# leds.net
KiCad netlist of a schematic drawn in Altium Designer
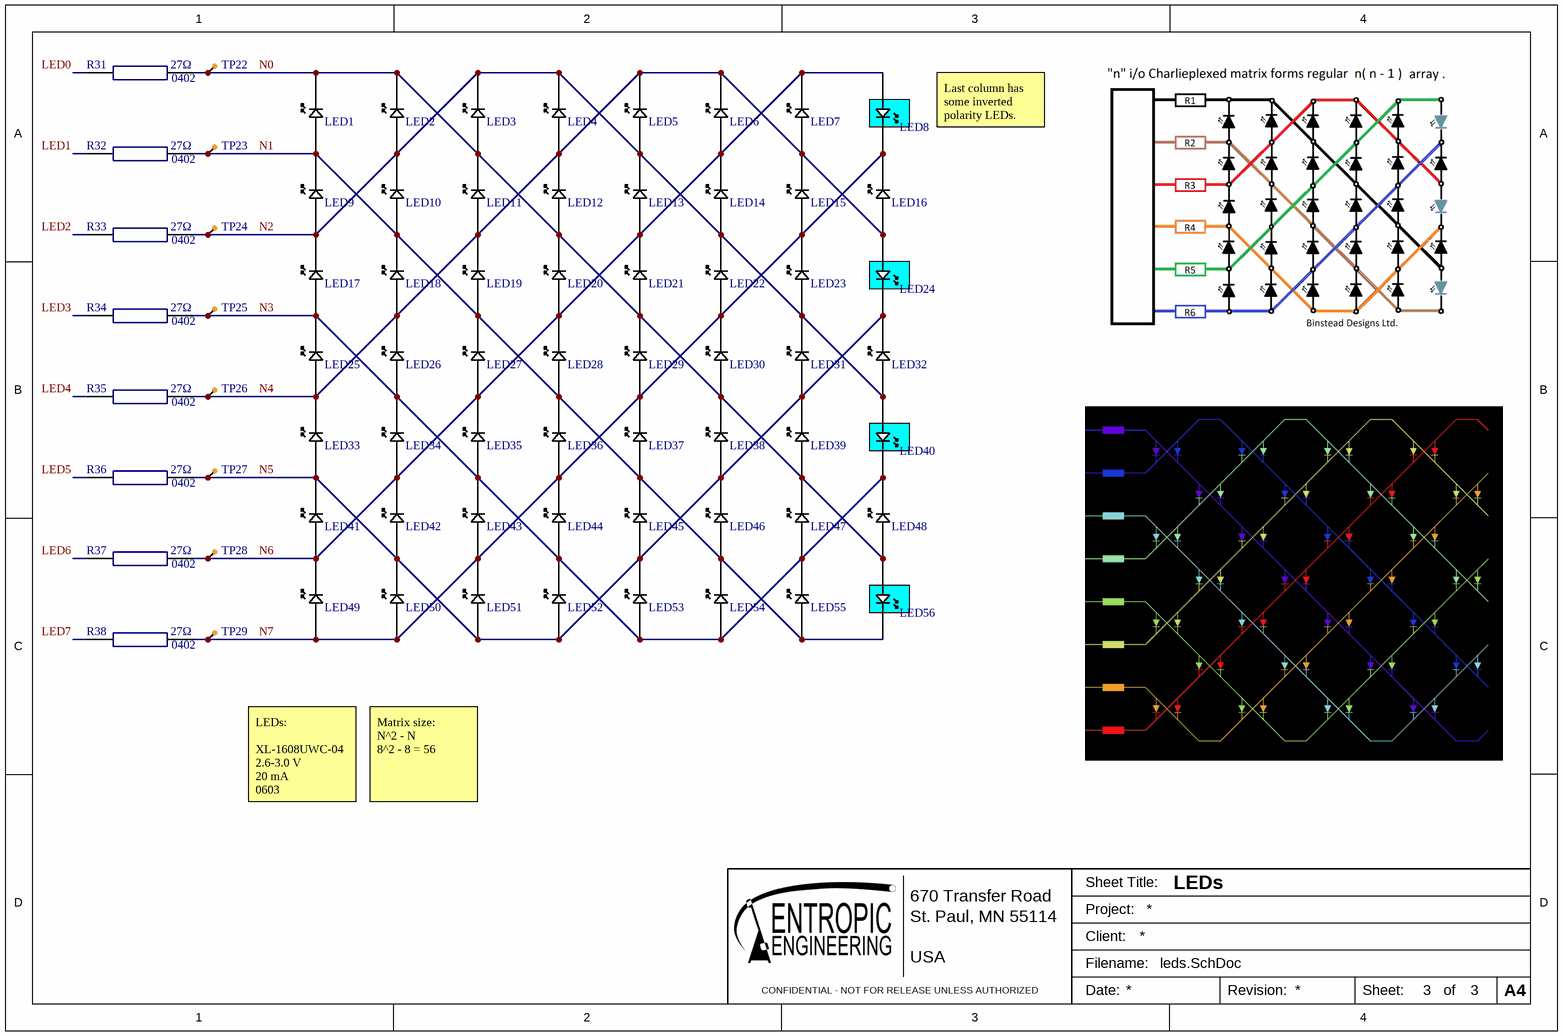
[diagram p0: leds.SchDoc]

(export (version "E")
  (design (tool "Eeschema 10.0.6"))
  (components
    (comp (ref "LED1")
      (value "XL-1608UWC-04")
      (footprint "0603_LED")
      (description "White LED, 0603")
      (fields (field (name "MANUFACTURER") "XINGLIGHT"))
      (libsource (lib "lamp_controller") (part "XL-1608UWC-04"))
    )
    (comp (ref "LED2")
      (value "XL-1608UWC-04")
      (footprint "0603_LED")
      (description "White LED, 0603")
      (fields (field (name "MANUFACTURER") "XINGLIGHT"))
      (libsource (lib "lamp_controller") (part "XL-1608UWC-04"))
    )
    (comp (ref "LED3")
      (value "XL-1608UWC-04")
      (footprint "0603_LED")
      (description "White LED, 0603")
      (fields (field (name "MANUFACTURER") "XINGLIGHT"))
      (libsource (lib "lamp_controller") (part "XL-1608UWC-04"))
    )
    (comp (ref "LED4")
      (value "XL-1608UWC-04")
      (footprint "0603_LED")
      (description "White LED, 0603")
      (fields (field (name "MANUFACTURER") "XINGLIGHT"))
      (libsource (lib "lamp_controller") (part "XL-1608UWC-04"))
    )
    (comp (ref "LED5")
      (value "XL-1608UWC-04")
      (footprint "0603_LED")
      (description "White LED, 0603")
      (fields (field (name "MANUFACTURER") "XINGLIGHT"))
      (libsource (lib "lamp_controller") (part "XL-1608UWC-04"))
    )
    (comp (ref "LED6")
      (value "XL-1608UWC-04")
      (footprint "0603_LED")
      (description "White LED, 0603")
      (fields (field (name "MANUFACTURER") "XINGLIGHT"))
      (libsource (lib "lamp_controller") (part "XL-1608UWC-04"))
    )
    (comp (ref "LED7")
      (value "XL-1608UWC-04")
      (footprint "0603_LED")
      (description "White LED, 0603")
      (fields (field (name "MANUFACTURER") "XINGLIGHT"))
      (libsource (lib "lamp_controller") (part "XL-1608UWC-04"))
    )
    (comp (ref "LED8")
      (value "XL-1608UWC-04")
      (footprint "0603_LED")
      (description "White LED, 0603")
      (fields (field (name "MANUFACTURER") "XINGLIGHT"))
      (libsource (lib "lamp_controller") (part "XL-1608UWC-04"))
    )
    (comp (ref "LED9")
      (value "XL-1608UWC-04")
      (footprint "0603_LED")
      (description "White LED, 0603")
      (fields (field (name "MANUFACTURER") "XINGLIGHT"))
      (libsource (lib "lamp_controller") (part "XL-1608UWC-04"))
    )
    (comp (ref "LED10")
      (value "XL-1608UWC-04")
      (footprint "0603_LED")
      (description "White LED, 0603")
      (fields (field (name "MANUFACTURER") "XINGLIGHT"))
      (libsource (lib "lamp_controller") (part "XL-1608UWC-04"))
    )
    (comp (ref "LED11")
      (value "XL-1608UWC-04")
      (footprint "0603_LED")
      (description "White LED, 0603")
      (fields (field (name "MANUFACTURER") "XINGLIGHT"))
      (libsource (lib "lamp_controller") (part "XL-1608UWC-04"))
    )
    (comp (ref "LED12")
      (value "XL-1608UWC-04")
      (footprint "0603_LED")
      (description "White LED, 0603")
      (fields (field (name "MANUFACTURER") "XINGLIGHT"))
      (libsource (lib "lamp_controller") (part "XL-1608UWC-04"))
    )
    (comp (ref "LED13")
      (value "XL-1608UWC-04")
      (footprint "0603_LED")
      (description "White LED, 0603")
      (fields (field (name "MANUFACTURER") "XINGLIGHT"))
      (libsource (lib "lamp_controller") (part "XL-1608UWC-04"))
    )
    (comp (ref "LED14")
      (value "XL-1608UWC-04")
      (footprint "0603_LED")
      (description "White LED, 0603")
      (fields (field (name "MANUFACTURER") "XINGLIGHT"))
      (libsource (lib "lamp_controller") (part "XL-1608UWC-04"))
    )
    (comp (ref "LED15")
      (value "XL-1608UWC-04")
      (footprint "0603_LED")
      (description "White LED, 0603")
      (fields (field (name "MANUFACTURER") "XINGLIGHT"))
      (libsource (lib "lamp_controller") (part "XL-1608UWC-04"))
    )
    (comp (ref "LED16")
      (value "XL-1608UWC-04")
      (footprint "0603_LED")
      (description "White LED, 0603")
      (fields (field (name "MANUFACTURER") "XINGLIGHT"))
      (libsource (lib "lamp_controller") (part "XL-1608UWC-04"))
    )
    (comp (ref "LED17")
      (value "XL-1608UWC-04")
      (footprint "0603_LED")
      (description "White LED, 0603")
      (fields (field (name "MANUFACTURER") "XINGLIGHT"))
      (libsource (lib "lamp_controller") (part "XL-1608UWC-04"))
    )
    (comp (ref "LED18")
      (value "XL-1608UWC-04")
      (footprint "0603_LED")
      (description "White LED, 0603")
      (fields (field (name "MANUFACTURER") "XINGLIGHT"))
      (libsource (lib "lamp_controller") (part "XL-1608UWC-04"))
    )
    (comp (ref "LED19")
      (value "XL-1608UWC-04")
      (footprint "0603_LED")
      (description "White LED, 0603")
      (fields (field (name "MANUFACTURER") "XINGLIGHT"))
      (libsource (lib "lamp_controller") (part "XL-1608UWC-04"))
    )
    (comp (ref "LED20")
      (value "XL-1608UWC-04")
      (footprint "0603_LED")
      (description "White LED, 0603")
      (fields (field (name "MANUFACTURER") "XINGLIGHT"))
      (libsource (lib "lamp_controller") (part "XL-1608UWC-04"))
    )
    (comp (ref "LED21")
      (value "XL-1608UWC-04")
      (footprint "0603_LED")
      (description "White LED, 0603")
      (fields (field (name "MANUFACTURER") "XINGLIGHT"))
      (libsource (lib "lamp_controller") (part "XL-1608UWC-04"))
    )
    (comp (ref "LED22")
      (value "XL-1608UWC-04")
      (footprint "0603_LED")
      (description "White LED, 0603")
      (fields (field (name "MANUFACTURER") "XINGLIGHT"))
      (libsource (lib "lamp_controller") (part "XL-1608UWC-04"))
    )
    (comp (ref "LED23")
      (value "XL-1608UWC-04")
      (footprint "0603_LED")
      (description "White LED, 0603")
      (fields (field (name "MANUFACTURER") "XINGLIGHT"))
      (libsource (lib "lamp_controller") (part "XL-1608UWC-04"))
    )
    (comp (ref "LED24")
      (value "XL-1608UWC-04")
      (footprint "0603_LED")
      (description "White LED, 0603")
      (fields (field (name "MANUFACTURER") "XINGLIGHT"))
      (libsource (lib "lamp_controller") (part "XL-1608UWC-04"))
    )
    (comp (ref "LED25")
      (value "XL-1608UWC-04")
      (footprint "0603_LED")
      (description "White LED, 0603")
      (fields (field (name "MANUFACTURER") "XINGLIGHT"))
      (libsource (lib "lamp_controller") (part "XL-1608UWC-04"))
    )
    (comp (ref "LED26")
      (value "XL-1608UWC-04")
      (footprint "0603_LED")
      (description "White LED, 0603")
      (fields (field (name "MANUFACTURER") "XINGLIGHT"))
      (libsource (lib "lamp_controller") (part "XL-1608UWC-04"))
    )
    (comp (ref "LED27")
      (value "XL-1608UWC-04")
      (footprint "0603_LED")
      (description "White LED, 0603")
      (fields (field (name "MANUFACTURER") "XINGLIGHT"))
      (libsource (lib "lamp_controller") (part "XL-1608UWC-04"))
    )
    (comp (ref "LED28")
      (value "XL-1608UWC-04")
      (footprint "0603_LED")
      (description "White LED, 0603")
      (fields (field (name "MANUFACTURER") "XINGLIGHT"))
      (libsource (lib "lamp_controller") (part "XL-1608UWC-04"))
    )
    (comp (ref "LED29")
      (value "XL-1608UWC-04")
      (footprint "0603_LED")
      (description "White LED, 0603")
      (fields (field (name "MANUFACTURER") "XINGLIGHT"))
      (libsource (lib "lamp_controller") (part "XL-1608UWC-04"))
    )
    (comp (ref "LED30")
      (value "XL-1608UWC-04")
      (footprint "0603_LED")
      (description "White LED, 0603")
      (fields (field (name "MANUFACTURER") "XINGLIGHT"))
      (libsource (lib "lamp_controller") (part "XL-1608UWC-04"))
    )
    (comp (ref "LED31")
      (value "XL-1608UWC-04")
      (footprint "0603_LED")
      (description "White LED, 0603")
      (fields (field (name "MANUFACTURER") "XINGLIGHT"))
      (libsource (lib "lamp_controller") (part "XL-1608UWC-04"))
    )
    (comp (ref "LED32")
      (value "XL-1608UWC-04")
      (footprint "0603_LED")
      (description "White LED, 0603")
      (fields (field (name "MANUFACTURER") "XINGLIGHT"))
      (libsource (lib "lamp_controller") (part "XL-1608UWC-04"))
    )
    (comp (ref "LED33")
      (value "XL-1608UWC-04")
      (footprint "0603_LED")
      (description "White LED, 0603")
      (fields (field (name "MANUFACTURER") "XINGLIGHT"))
      (libsource (lib "lamp_controller") (part "XL-1608UWC-04"))
    )
    (comp (ref "LED34")
      (value "XL-1608UWC-04")
      (footprint "0603_LED")
      (description "White LED, 0603")
      (fields (field (name "MANUFACTURER") "XINGLIGHT"))
      (libsource (lib "lamp_controller") (part "XL-1608UWC-04"))
    )
    (comp (ref "LED35")
      (value "XL-1608UWC-04")
      (footprint "0603_LED")
      (description "White LED, 0603")
      (fields (field (name "MANUFACTURER") "XINGLIGHT"))
      (libsource (lib "lamp_controller") (part "XL-1608UWC-04"))
    )
    (comp (ref "LED36")
      (value "XL-1608UWC-04")
      (footprint "0603_LED")
      (description "White LED, 0603")
      (fields (field (name "MANUFACTURER") "XINGLIGHT"))
      (libsource (lib "lamp_controller") (part "XL-1608UWC-04"))
    )
    (comp (ref "LED37")
      (value "XL-1608UWC-04")
      (footprint "0603_LED")
      (description "White LED, 0603")
      (fields (field (name "MANUFACTURER") "XINGLIGHT"))
      (libsource (lib "lamp_controller") (part "XL-1608UWC-04"))
    )
    (comp (ref "LED38")
      (value "XL-1608UWC-04")
      (footprint "0603_LED")
      (description "White LED, 0603")
      (fields (field (name "MANUFACTURER") "XINGLIGHT"))
      (libsource (lib "lamp_controller") (part "XL-1608UWC-04"))
    )
    (comp (ref "LED39")
      (value "XL-1608UWC-04")
      (footprint "0603_LED")
      (description "White LED, 0603")
      (fields (field (name "MANUFACTURER") "XINGLIGHT"))
      (libsource (lib "lamp_controller") (part "XL-1608UWC-04"))
    )
    (comp (ref "LED40")
      (value "XL-1608UWC-04")
      (footprint "0603_LED")
      (description "White LED, 0603")
      (fields (field (name "MANUFACTURER") "XINGLIGHT"))
      (libsource (lib "lamp_controller") (part "XL-1608UWC-04"))
    )
    (comp (ref "LED41")
      (value "XL-1608UWC-04")
      (footprint "0603_LED")
      (description "White LED, 0603")
      (fields (field (name "MANUFACTURER") "XINGLIGHT"))
      (libsource (lib "lamp_controller") (part "XL-1608UWC-04"))
    )
    (comp (ref "LED42")
      (value "XL-1608UWC-04")
      (footprint "0603_LED")
      (description "White LED, 0603")
      (fields (field (name "MANUFACTURER") "XINGLIGHT"))
      (libsource (lib "lamp_controller") (part "XL-1608UWC-04"))
    )
    (comp (ref "LED43")
      (value "XL-1608UWC-04")
      (footprint "0603_LED")
      (description "White LED, 0603")
      (fields (field (name "MANUFACTURER") "XINGLIGHT"))
      (libsource (lib "lamp_controller") (part "XL-1608UWC-04"))
    )
    (comp (ref "LED44")
      (value "XL-1608UWC-04")
      (footprint "0603_LED")
      (description "White LED, 0603")
      (fields (field (name "MANUFACTURER") "XINGLIGHT"))
      (libsource (lib "lamp_controller") (part "XL-1608UWC-04"))
    )
    (comp (ref "LED45")
      (value "XL-1608UWC-04")
      (footprint "0603_LED")
      (description "White LED, 0603")
      (fields (field (name "MANUFACTURER") "XINGLIGHT"))
      (libsource (lib "lamp_controller") (part "XL-1608UWC-04"))
    )
    (comp (ref "LED46")
      (value "XL-1608UWC-04")
      (footprint "0603_LED")
      (description "White LED, 0603")
      (fields (field (name "MANUFACTURER") "XINGLIGHT"))
      (libsource (lib "lamp_controller") (part "XL-1608UWC-04"))
    )
    (comp (ref "LED47")
      (value "XL-1608UWC-04")
      (footprint "0603_LED")
      (description "White LED, 0603")
      (fields (field (name "MANUFACTURER") "XINGLIGHT"))
      (libsource (lib "lamp_controller") (part "XL-1608UWC-04"))
    )
    (comp (ref "LED48")
      (value "XL-1608UWC-04")
      (footprint "0603_LED")
      (description "White LED, 0603")
      (fields (field (name "MANUFACTURER") "XINGLIGHT"))
      (libsource (lib "lamp_controller") (part "XL-1608UWC-04"))
    )
    (comp (ref "LED49")
      (value "XL-1608UWC-04")
      (footprint "0603_LED")
      (description "White LED, 0603")
      (fields (field (name "MANUFACTURER") "XINGLIGHT"))
      (libsource (lib "lamp_controller") (part "XL-1608UWC-04"))
    )
    (comp (ref "LED50")
      (value "XL-1608UWC-04")
      (footprint "0603_LED")
      (description "White LED, 0603")
      (fields (field (name "MANUFACTURER") "XINGLIGHT"))
      (libsource (lib "lamp_controller") (part "XL-1608UWC-04"))
    )
    (comp (ref "LED51")
      (value "XL-1608UWC-04")
      (footprint "0603_LED")
      (description "White LED, 0603")
      (fields (field (name "MANUFACTURER") "XINGLIGHT"))
      (libsource (lib "lamp_controller") (part "XL-1608UWC-04"))
    )
    (comp (ref "LED52")
      (value "XL-1608UWC-04")
      (footprint "0603_LED")
      (description "White LED, 0603")
      (fields (field (name "MANUFACTURER") "XINGLIGHT"))
      (libsource (lib "lamp_controller") (part "XL-1608UWC-04"))
    )
    (comp (ref "LED53")
      (value "XL-1608UWC-04")
      (footprint "0603_LED")
      (description "White LED, 0603")
      (fields (field (name "MANUFACTURER") "XINGLIGHT"))
      (libsource (lib "lamp_controller") (part "XL-1608UWC-04"))
    )
    (comp (ref "LED54")
      (value "XL-1608UWC-04")
      (footprint "0603_LED")
      (description "White LED, 0603")
      (fields (field (name "MANUFACTURER") "XINGLIGHT"))
      (libsource (lib "lamp_controller") (part "XL-1608UWC-04"))
    )
    (comp (ref "LED55")
      (value "XL-1608UWC-04")
      (footprint "0603_LED")
      (description "White LED, 0603")
      (fields (field (name "MANUFACTURER") "XINGLIGHT"))
      (libsource (lib "lamp_controller") (part "XL-1608UWC-04"))
    )
    (comp (ref "LED56")
      (value "XL-1608UWC-04")
      (footprint "0603_LED")
      (description "White LED, 0603")
      (fields (field (name "MANUFACTURER") "XINGLIGHT"))
      (libsource (lib "lamp_controller") (part "XL-1608UWC-04"))
    )
    (comp (ref "R31")
      (value "RMCF0402FT27R0")
      (footprint "0402_resistor")
      (description "27 Ω, 0402 Chip resistor")
      (fields
        (field (name "MANUFACTURER") "Stackpole Electronics")
        (field (name "TOLERANCE") "1%")
        (field (name "RESISTANCE") "27Ω")
        (field (name "SIZE CODE") "0402")
      )
      (libsource (lib "lamp_controller") (part "RMCF0402FT27R0"))
    )
    (comp (ref "R32")
      (value "RMCF0402FT27R0")
      (footprint "0402_resistor")
      (description "27 Ω, 0402 Chip resistor")
      (fields
        (field (name "MANUFACTURER") "Stackpole Electronics")
        (field (name "TOLERANCE") "1%")
        (field (name "RESISTANCE") "27Ω")
        (field (name "SIZE CODE") "0402")
      )
      (libsource (lib "lamp_controller") (part "RMCF0402FT27R0"))
    )
    (comp (ref "R33")
      (value "RMCF0402FT27R0")
      (footprint "0402_resistor")
      (description "27 Ω, 0402 Chip resistor")
      (fields
        (field (name "MANUFACTURER") "Stackpole Electronics")
        (field (name "TOLERANCE") "1%")
        (field (name "RESISTANCE") "27Ω")
        (field (name "SIZE CODE") "0402")
      )
      (libsource (lib "lamp_controller") (part "RMCF0402FT27R0"))
    )
    (comp (ref "R34")
      (value "RMCF0402FT27R0")
      (footprint "0402_resistor")
      (description "27 Ω, 0402 Chip resistor")
      (fields
        (field (name "MANUFACTURER") "Stackpole Electronics")
        (field (name "TOLERANCE") "1%")
        (field (name "RESISTANCE") "27Ω")
        (field (name "SIZE CODE") "0402")
      )
      (libsource (lib "lamp_controller") (part "RMCF0402FT27R0"))
    )
    (comp (ref "R35")
      (value "RMCF0402FT27R0")
      (footprint "0402_resistor")
      (description "27 Ω, 0402 Chip resistor")
      (fields
        (field (name "MANUFACTURER") "Stackpole Electronics")
        (field (name "TOLERANCE") "1%")
        (field (name "RESISTANCE") "27Ω")
        (field (name "SIZE CODE") "0402")
      )
      (libsource (lib "lamp_controller") (part "RMCF0402FT27R0"))
    )
    (comp (ref "R36")
      (value "RMCF0402FT27R0")
      (footprint "0402_resistor")
      (description "27 Ω, 0402 Chip resistor")
      (fields
        (field (name "MANUFACTURER") "Stackpole Electronics")
        (field (name "TOLERANCE") "1%")
        (field (name "RESISTANCE") "27Ω")
        (field (name "SIZE CODE") "0402")
      )
      (libsource (lib "lamp_controller") (part "RMCF0402FT27R0"))
    )
    (comp (ref "R37")
      (value "RMCF0402FT27R0")
      (footprint "0402_resistor")
      (description "27 Ω, 0402 Chip resistor")
      (fields
        (field (name "MANUFACTURER") "Stackpole Electronics")
        (field (name "TOLERANCE") "1%")
        (field (name "RESISTANCE") "27Ω")
        (field (name "SIZE CODE") "0402")
      )
      (libsource (lib "lamp_controller") (part "RMCF0402FT27R0"))
    )
    (comp (ref "R38")
      (value "RMCF0402FT27R0")
      (footprint "0402_resistor")
      (description "27 Ω, 0402 Chip resistor")
      (fields
        (field (name "MANUFACTURER") "Stackpole Electronics")
        (field (name "TOLERANCE") "1%")
        (field (name "RESISTANCE") "27Ω")
        (field (name "SIZE CODE") "0402")
      )
      (libsource (lib "lamp_controller") (part "RMCF0402FT27R0"))
    )
    (comp (ref "TP22")
      (value "test_point-1")
      (footprint "test_point-1")
      (description "Test point")
      (libsource (lib "lamp_controller") (part "test_point-1"))
    )
    (comp (ref "TP23")
      (value "test_point-1")
      (footprint "test_point-1")
      (description "Test point")
      (libsource (lib "lamp_controller") (part "test_point-1"))
    )
    (comp (ref "TP24")
      (value "test_point-1")
      (footprint "test_point-1")
      (description "Test point")
      (libsource (lib "lamp_controller") (part "test_point-1"))
    )
    (comp (ref "TP25")
      (value "test_point-1")
      (footprint "test_point-1")
      (description "Test point")
      (libsource (lib "lamp_controller") (part "test_point-1"))
    )
    (comp (ref "TP26")
      (value "test_point-1")
      (footprint "test_point-1")
      (description "Test point")
      (libsource (lib "lamp_controller") (part "test_point-1"))
    )
    (comp (ref "TP27")
      (value "test_point-1")
      (footprint "test_point-1")
      (description "Test point")
      (libsource (lib "lamp_controller") (part "test_point-1"))
    )
    (comp (ref "TP28")
      (value "test_point-1")
      (footprint "test_point-1")
      (description "Test point")
      (libsource (lib "lamp_controller") (part "test_point-1"))
    )
    (comp (ref "TP29")
      (value "test_point-1")
      (footprint "test_point-1")
      (description "Test point")
      (libsource (lib "lamp_controller") (part "test_point-1"))
    )
  )
  (nets
    (net (code "1") (name "/LED0") (class "Default")
      (node (ref "R31") (pin "2") (pinfunction "2_2") (pintype "passive"))
    )
    (net (code "2") (name "/LED1") (class "Default")
      (node (ref "R32") (pin "2") (pinfunction "2_2") (pintype "passive"))
    )
    (net (code "3") (name "/LED2") (class "Default")
      (node (ref "R33") (pin "2") (pinfunction "2_2") (pintype "passive"))
    )
    (net (code "4") (name "/LED3") (class "Default")
      (node (ref "R34") (pin "2") (pinfunction "2_2") (pintype "passive"))
    )
    (net (code "5") (name "/LED4") (class "Default")
      (node (ref "R35") (pin "2") (pinfunction "2_2") (pintype "passive"))
    )
    (net (code "6") (name "/LED5") (class "Default")
      (node (ref "R36") (pin "2") (pinfunction "2_2") (pintype "passive"))
    )
    (net (code "7") (name "/LED6") (class "Default")
      (node (ref "R37") (pin "2") (pinfunction "2_2") (pintype "passive"))
    )
    (net (code "8") (name "/LED7") (class "Default")
      (node (ref "R38") (pin "2") (pinfunction "2_2") (pintype "passive"))
    )
    (net (code "9") (name "/N0") (class "Default")
      (node (ref "LED1") (pin "2") (pinfunction "K_2") (pintype "passive"))
      (node (ref "LED11") (pin "2") (pinfunction "K_2") (pintype "passive"))
      (node (ref "LED12") (pin "1") (pinfunction "A_1") (pintype "passive"))
      (node (ref "LED2") (pin "2") (pinfunction "K_2") (pintype "passive"))
      (node (ref "LED20") (pin "2") (pinfunction "K_2") (pintype "passive"))
      (node (ref "LED21") (pin "1") (pinfunction "A_1") (pintype "passive"))
      (node (ref "LED29") (pin "2") (pinfunction "K_2") (pintype "passive"))
      (node (ref "LED3") (pin "1") (pinfunction "A_1") (pintype "passive"))
      (node (ref "LED30") (pin "1") (pinfunction "A_1") (pintype "passive"))
      (node (ref "LED38") (pin "2") (pinfunction "K_2") (pintype "passive"))
      (node (ref "LED39") (pin "1") (pinfunction "A_1") (pintype "passive"))
      (node (ref "LED47") (pin "2") (pinfunction "K_2") (pintype "passive"))
      (node (ref "LED48") (pin "1") (pinfunction "A_1") (pintype "passive"))
      (node (ref "LED56") (pin "1") (pinfunction "A_1") (pintype "passive"))
      (node (ref "R31") (pin "1") (pinfunction "1_1") (pintype "passive"))
      (node (ref "TP22") (pin "1") (pinfunction "1_1") (pintype "passive"))
    )
    (net (code "10") (name "/N1") (class "Default")
      (node (ref "LED1") (pin "1") (pinfunction "A_1") (pintype "passive"))
      (node (ref "LED10") (pin "1") (pinfunction "A_1") (pintype "passive"))
      (node (ref "LED18") (pin "2") (pinfunction "K_2") (pintype "passive"))
      (node (ref "LED19") (pin "1") (pinfunction "A_1") (pintype "passive"))
      (node (ref "LED27") (pin "2") (pinfunction "K_2") (pintype "passive"))
      (node (ref "LED28") (pin "1") (pinfunction "A_1") (pintype "passive"))
      (node (ref "LED36") (pin "2") (pinfunction "K_2") (pintype "passive"))
      (node (ref "LED37") (pin "1") (pinfunction "A_1") (pintype "passive"))
      (node (ref "LED45") (pin "2") (pinfunction "K_2") (pintype "passive"))
      (node (ref "LED46") (pin "1") (pinfunction "A_1") (pintype "passive"))
      (node (ref "LED54") (pin "2") (pinfunction "K_2") (pintype "passive"))
      (node (ref "LED55") (pin "1") (pinfunction "A_1") (pintype "passive"))
      (node (ref "LED56") (pin "2") (pinfunction "K_2") (pintype "passive"))
      (node (ref "LED9") (pin "2") (pinfunction "K_2") (pintype "passive"))
      (node (ref "R32") (pin "1") (pinfunction "1_1") (pintype "passive"))
      (node (ref "TP23") (pin "1") (pinfunction "1_1") (pintype "passive"))
    )
    (net (code "11") (name "/N2") (class "Default")
      (node (ref "LED10") (pin "2") (pinfunction "K_2") (pintype "passive"))
      (node (ref "LED13") (pin "2") (pinfunction "K_2") (pintype "passive"))
      (node (ref "LED14") (pin "1") (pinfunction "A_1") (pintype "passive"))
      (node (ref "LED17") (pin "2") (pinfunction "K_2") (pintype "passive"))
      (node (ref "LED2") (pin "1") (pinfunction "A_1") (pintype "passive"))
      (node (ref "LED22") (pin "2") (pinfunction "K_2") (pintype "passive"))
      (node (ref "LED23") (pin "1") (pinfunction "A_1") (pintype "passive"))
      (node (ref "LED3") (pin "2") (pinfunction "K_2") (pintype "passive"))
      (node (ref "LED31") (pin "2") (pinfunction "K_2") (pintype "passive"))
      (node (ref "LED32") (pin "1") (pinfunction "A_1") (pintype "passive"))
      (node (ref "LED4") (pin "2") (pinfunction "K_2") (pintype "passive"))
      (node (ref "LED40") (pin "1") (pinfunction "A_1") (pintype "passive"))
      (node (ref "LED5") (pin "1") (pinfunction "A_1") (pintype "passive"))
      (node (ref "LED9") (pin "1") (pinfunction "A_1") (pintype "passive"))
      (node (ref "R33") (pin "1") (pinfunction "1_1") (pintype "passive"))
      (node (ref "TP24") (pin "1") (pinfunction "1_1") (pintype "passive"))
    )
    (net (code "12") (name "/N3") (class "Default")
      (node (ref "LED17") (pin "1") (pinfunction "A_1") (pintype "passive"))
      (node (ref "LED25") (pin "2") (pinfunction "K_2") (pintype "passive"))
      (node (ref "LED26") (pin "1") (pinfunction "A_1") (pintype "passive"))
      (node (ref "LED34") (pin "2") (pinfunction "K_2") (pintype "passive"))
      (node (ref "LED35") (pin "1") (pinfunction "A_1") (pintype "passive"))
      (node (ref "LED40") (pin "2") (pinfunction "K_2") (pintype "passive"))
      (node (ref "LED43") (pin "2") (pinfunction "K_2") (pintype "passive"))
      (node (ref "LED44") (pin "1") (pinfunction "A_1") (pintype "passive"))
      (node (ref "LED47") (pin "1") (pinfunction "A_1") (pintype "passive"))
      (node (ref "LED48") (pin "2") (pinfunction "K_2") (pintype "passive"))
      (node (ref "LED52") (pin "2") (pinfunction "K_2") (pintype "passive"))
      (node (ref "LED53") (pin "1") (pinfunction "A_1") (pintype "passive"))
      (node (ref "LED54") (pin "1") (pinfunction "A_1") (pintype "passive"))
      (node (ref "LED55") (pin "2") (pinfunction "K_2") (pintype "passive"))
      (node (ref "R34") (pin "1") (pinfunction "1_1") (pintype "passive"))
      (node (ref "TP25") (pin "1") (pinfunction "1_1") (pintype "passive"))
    )
    (net (code "13") (name "/N4") (class "Default")
      (node (ref "LED11") (pin "1") (pinfunction "A_1") (pintype "passive"))
      (node (ref "LED12") (pin "2") (pinfunction "K_2") (pintype "passive"))
      (node (ref "LED15") (pin "2") (pinfunction "K_2") (pintype "passive"))
      (node (ref "LED16") (pin "1") (pinfunction "A_1") (pintype "passive"))
      (node (ref "LED18") (pin "1") (pinfunction "A_1") (pintype "passive"))
      (node (ref "LED19") (pin "2") (pinfunction "K_2") (pintype "passive"))
      (node (ref "LED24") (pin "1") (pinfunction "A_1") (pintype "passive"))
      (node (ref "LED25") (pin "1") (pinfunction "A_1") (pintype "passive"))
      (node (ref "LED26") (pin "2") (pinfunction "K_2") (pintype "passive"))
      (node (ref "LED33") (pin "2") (pinfunction "K_2") (pintype "passive"))
      (node (ref "LED4") (pin "1") (pinfunction "A_1") (pintype "passive"))
      (node (ref "LED5") (pin "2") (pinfunction "K_2") (pintype "passive"))
      (node (ref "LED6") (pin "2") (pinfunction "K_2") (pintype "passive"))
      (node (ref "LED7") (pin "1") (pinfunction "A_1") (pintype "passive"))
      (node (ref "R35") (pin "1") (pinfunction "1_1") (pintype "passive"))
      (node (ref "TP26") (pin "1") (pinfunction "1_1") (pintype "passive"))
    )
    (net (code "14") (name "/N5") (class "Default")
      (node (ref "LED24") (pin "2") (pinfunction "K_2") (pintype "passive"))
      (node (ref "LED31") (pin "1") (pinfunction "A_1") (pintype "passive"))
      (node (ref "LED32") (pin "2") (pinfunction "K_2") (pintype "passive"))
      (node (ref "LED33") (pin "1") (pinfunction "A_1") (pintype "passive"))
      (node (ref "LED38") (pin "1") (pinfunction "A_1") (pintype "passive"))
      (node (ref "LED39") (pin "2") (pinfunction "K_2") (pintype "passive"))
      (node (ref "LED41") (pin "2") (pinfunction "K_2") (pintype "passive"))
      (node (ref "LED42") (pin "1") (pinfunction "A_1") (pintype "passive"))
      (node (ref "LED45") (pin "1") (pinfunction "A_1") (pintype "passive"))
      (node (ref "LED46") (pin "2") (pinfunction "K_2") (pintype "passive"))
      (node (ref "LED50") (pin "2") (pinfunction "K_2") (pintype "passive"))
      (node (ref "LED51") (pin "1") (pinfunction "A_1") (pintype "passive"))
      (node (ref "LED52") (pin "1") (pinfunction "A_1") (pintype "passive"))
      (node (ref "LED53") (pin "2") (pinfunction "K_2") (pintype "passive"))
      (node (ref "R36") (pin "1") (pinfunction "1_1") (pintype "passive"))
      (node (ref "TP27") (pin "1") (pinfunction "1_1") (pintype "passive"))
    )
    (net (code "15") (name "/N6") (class "Default")
      (node (ref "LED13") (pin "1") (pinfunction "A_1") (pintype "passive"))
      (node (ref "LED14") (pin "2") (pinfunction "K_2") (pintype "passive"))
      (node (ref "LED20") (pin "1") (pinfunction "A_1") (pintype "passive"))
      (node (ref "LED21") (pin "2") (pinfunction "K_2") (pintype "passive"))
      (node (ref "LED27") (pin "1") (pinfunction "A_1") (pintype "passive"))
      (node (ref "LED28") (pin "2") (pinfunction "K_2") (pintype "passive"))
      (node (ref "LED34") (pin "1") (pinfunction "A_1") (pintype "passive"))
      (node (ref "LED35") (pin "2") (pinfunction "K_2") (pintype "passive"))
      (node (ref "LED41") (pin "1") (pinfunction "A_1") (pintype "passive"))
      (node (ref "LED42") (pin "2") (pinfunction "K_2") (pintype "passive"))
      (node (ref "LED49") (pin "2") (pinfunction "K_2") (pintype "passive"))
      (node (ref "LED6") (pin "1") (pinfunction "A_1") (pintype "passive"))
      (node (ref "LED7") (pin "2") (pinfunction "K_2") (pintype "passive"))
      (node (ref "LED8") (pin "1") (pinfunction "A_1") (pintype "passive"))
      (node (ref "R37") (pin "1") (pinfunction "1_1") (pintype "passive"))
      (node (ref "TP28") (pin "1") (pinfunction "1_1") (pintype "passive"))
    )
    (net (code "16") (name "/N7") (class "Default")
      (node (ref "LED15") (pin "1") (pinfunction "A_1") (pintype "passive"))
      (node (ref "LED16") (pin "2") (pinfunction "K_2") (pintype "passive"))
      (node (ref "LED22") (pin "1") (pinfunction "A_1") (pintype "passive"))
      (node (ref "LED23") (pin "2") (pinfunction "K_2") (pintype "passive"))
      (node (ref "LED29") (pin "1") (pinfunction "A_1") (pintype "passive"))
      (node (ref "LED30") (pin "2") (pinfunction "K_2") (pintype "passive"))
      (node (ref "LED36") (pin "1") (pinfunction "A_1") (pintype "passive"))
      (node (ref "LED37") (pin "2") (pinfunction "K_2") (pintype "passive"))
      (node (ref "LED43") (pin "1") (pinfunction "A_1") (pintype "passive"))
      (node (ref "LED44") (pin "2") (pinfunction "K_2") (pintype "passive"))
      (node (ref "LED49") (pin "1") (pinfunction "A_1") (pintype "passive"))
      (node (ref "LED50") (pin "1") (pinfunction "A_1") (pintype "passive"))
      (node (ref "LED51") (pin "2") (pinfunction "K_2") (pintype "passive"))
      (node (ref "LED8") (pin "2") (pinfunction "K_2") (pintype "passive"))
      (node (ref "R38") (pin "1") (pinfunction "1_1") (pintype "passive"))
      (node (ref "TP29") (pin "1") (pinfunction "1_1") (pintype "passive"))
    )
  )
)
